# DDR4_SODIMM2.net
KiCad netlist of a schematic drawn in Altium Designer
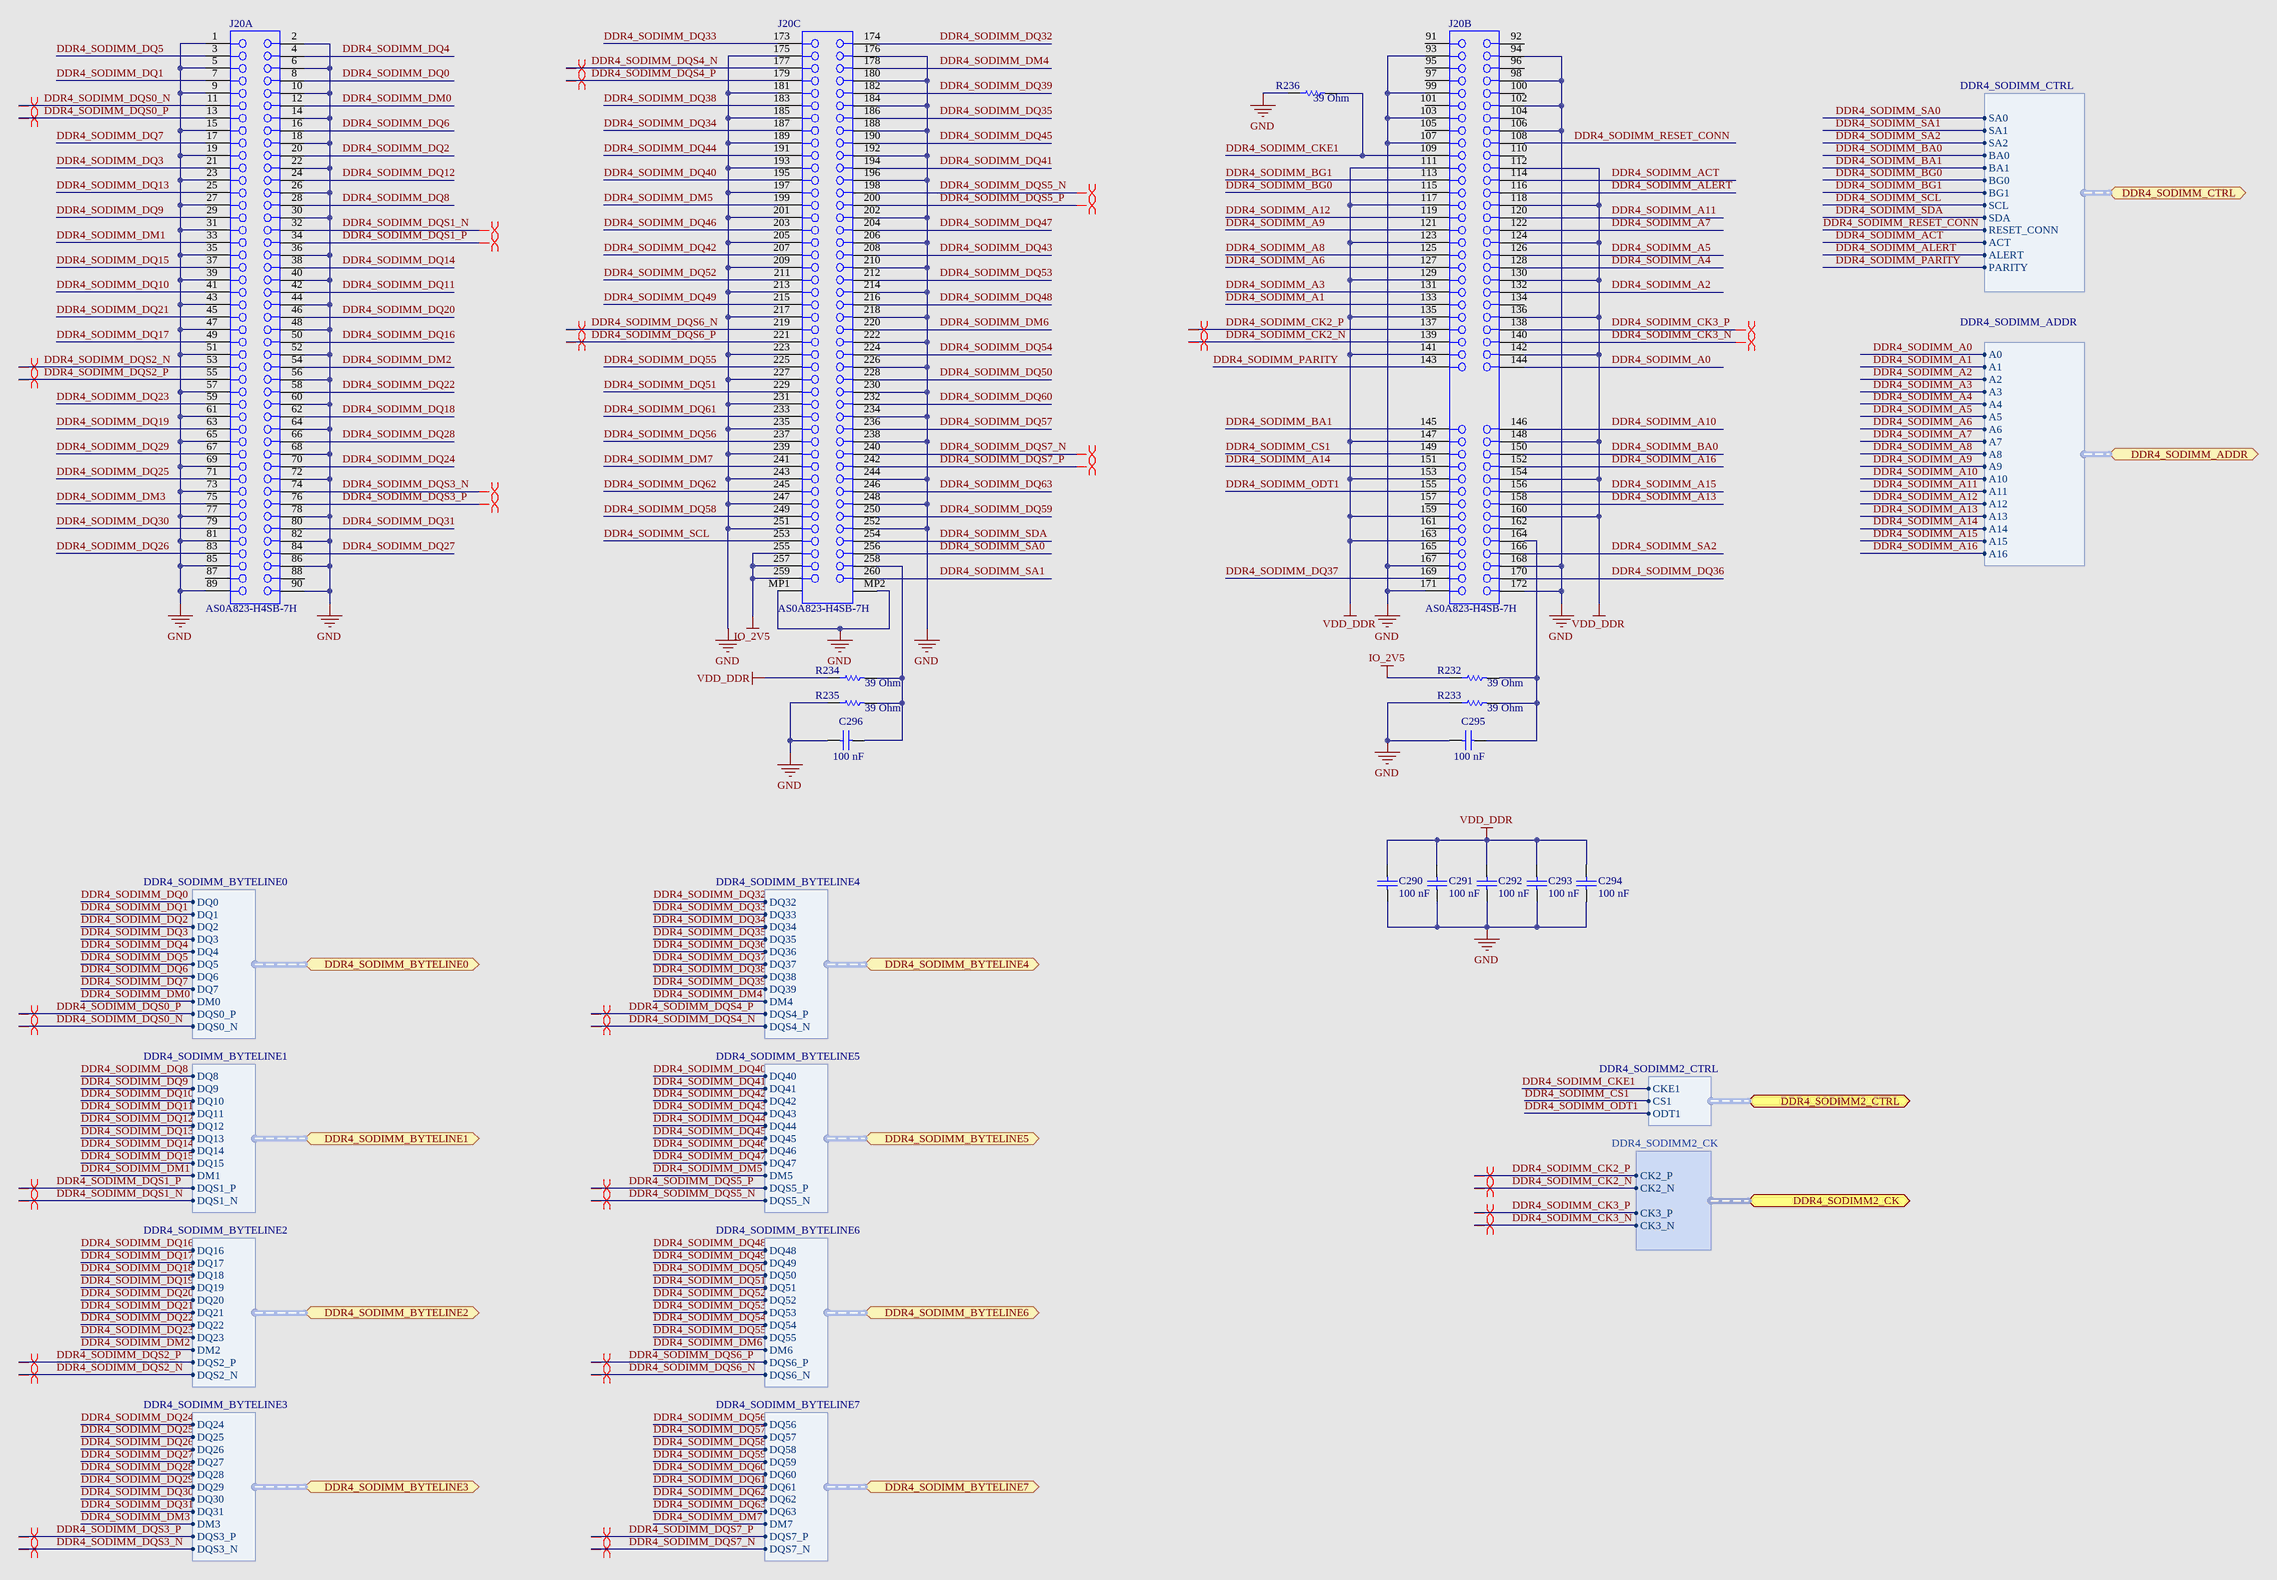
[diagram p0: DDR4_SODIMM2.SchDoc]

(export (version "E")
  (design (tool "Eeschema 10.0.6"))
  (components
    (comp (ref "C290")
      (value "C1005X7R1E104M")
      (footprint "CAPC1005X55X10LL05")
      (description "Chip Capacitor, 0.1 uF, +/- 20%, 25 V, -55 to 125 degC, 0402 (1005 Metric), RoHS, Tape and Reel")
      (fields (field (name "TOLERANCE") "20%") (field (name "CAPACITANCE") "100 nF"))
      (libsource (lib "Altium Content Vault") (part "CAP-NP-2"))
    )
    (comp (ref "C291")
      (value "C1005X7R1E104M")
      (footprint "CAPC1005X55X10LL05")
      (description "Chip Capacitor, 0.1 uF, +/- 20%, 25 V, -55 to 125 degC, 0402 (1005 Metric), RoHS, Tape and Reel")
      (fields (field (name "TOLERANCE") "20%") (field (name "CAPACITANCE") "100 nF"))
      (libsource (lib "Altium Content Vault") (part "CAP-NP-2"))
    )
    (comp (ref "C292")
      (value "C1005X7R1E104M")
      (footprint "CAPC1005X55X10LL05")
      (description "Chip Capacitor, 0.1 uF, +/- 20%, 25 V, -55 to 125 degC, 0402 (1005 Metric), RoHS, Tape and Reel")
      (fields (field (name "TOLERANCE") "20%") (field (name "CAPACITANCE") "100 nF"))
      (libsource (lib "Altium Content Vault") (part "CAP-NP-2"))
    )
    (comp (ref "C293")
      (value "C1005X7R1E104M")
      (footprint "CAPC1005X55X10LL05")
      (description "Chip Capacitor, 0.1 uF, +/- 20%, 25 V, -55 to 125 degC, 0402 (1005 Metric), RoHS, Tape and Reel")
      (fields (field (name "TOLERANCE") "20%") (field (name "CAPACITANCE") "100 nF"))
      (libsource (lib "Altium Content Vault") (part "CAP-NP-2"))
    )
    (comp (ref "C294")
      (value "C1005X7R1E104M")
      (footprint "CAPC1005X55X10LL05")
      (description "Chip Capacitor, 0.1 uF, +/- 20%, 25 V, -55 to 125 degC, 0402 (1005 Metric), RoHS, Tape and Reel")
      (fields (field (name "TOLERANCE") "20%") (field (name "CAPACITANCE") "100 nF"))
      (libsource (lib "Altium Content Vault") (part "CAP-NP-2"))
    )
    (comp (ref "C295")
      (value "C1005X7R1E104M")
      (footprint "CAPC1005X55X10LL05")
      (description "Chip Capacitor, 0.1 uF, +/- 20%, 25 V, -55 to 125 degC, 0402 (1005 Metric), RoHS, Tape and Reel")
      (fields (field (name "TOLERANCE") "20%") (field (name "CAPACITANCE") "100 nF"))
      (libsource (lib "Altium Content Vault") (part "CAP-NP-2"))
    )
    (comp (ref "C296")
      (value "C1005X7R1E104M")
      (footprint "CAPC1005X55X10LL05")
      (description "Chip Capacitor, 0.1 uF, +/- 20%, 25 V, -55 to 125 degC, 0402 (1005 Metric), RoHS, Tape and Reel")
      (fields (field (name "TOLERANCE") "20%") (field (name "CAPACITANCE") "100 nF"))
      (libsource (lib "Altium Content Vault") (part "CAP-NP-2"))
    )
    (comp (ref "J20")
      (value "AS0A823-H4SB-7H")
      (footprint "FOXC-AS0A823-H4SB-7H_V")
      (libsource (lib "") (part "CN-2S-2F-R260_1"))
    )
    (comp (ref "R232")
      (value "NRC04F49R9TRF")
      (footprint "RESC1005X35X25NL8T10")
      (description "Chip Resistor, 39 Ohm, +/- 5%, 0.063 W, -55 to 155 degC, 0402 (1005 Metric), RoHS, Tape and Reel")
      (fields
        (field (name "PARTNUMBER") "RC0402JR-0739RL")
        (field (name "TOLERANCE") "5%")
        (field (name "RESISTANCE") "39 Ohm")
      )
      (libsource (lib "Altium Content Vault") (part "CMP-2002-07994-2"))
    )
    (comp (ref "R233")
      (value "NRC04F49R9TRF")
      (footprint "RESC1005X35X25NL8T10")
      (description "Chip Resistor, 39 Ohm, +/- 5%, 0.063 W, -55 to 155 degC, 0402 (1005 Metric), RoHS, Tape and Reel")
      (fields
        (field (name "PARTNUMBER") "RC0402JR-0739RL")
        (field (name "TOLERANCE") "5%")
        (field (name "RESISTANCE") "39 Ohm")
      )
      (libsource (lib "Altium Content Vault") (part "CMP-2002-07994-2"))
    )
    (comp (ref "R234")
      (value "NRC04F49R9TRF")
      (footprint "RESC1005X35X25NL8T10")
      (description "Chip Resistor, 39 Ohm, +/- 5%, 0.063 W, -55 to 155 degC, 0402 (1005 Metric), RoHS, Tape and Reel")
      (fields
        (field (name "PARTNUMBER") "RC0402JR-0739RL")
        (field (name "TOLERANCE") "5%")
        (field (name "RESISTANCE") "39 Ohm")
      )
      (libsource (lib "Altium Content Vault") (part "CMP-2002-07994-2"))
    )
    (comp (ref "R235")
      (value "NRC04F49R9TRF")
      (footprint "RESC1005X35X25NL8T10")
      (description "Chip Resistor, 39 Ohm, +/- 5%, 0.063 W, -55 to 155 degC, 0402 (1005 Metric), RoHS, Tape and Reel")
      (fields
        (field (name "PARTNUMBER") "RC0402JR-0739RL")
        (field (name "TOLERANCE") "5%")
        (field (name "RESISTANCE") "39 Ohm")
      )
      (libsource (lib "Altium Content Vault") (part "CMP-2002-07994-2"))
    )
    (comp (ref "R236")
      (value "RC0402JR-0739RL")
      (footprint "RESC1005X40X25NL5T10")
      (description "Chip Resistor, 39 Ohm, +/- 5%, 0.063 W, -55 to 155 degC, 0402 (1005 Metric), RoHS, Tape and Reel")
      (fields (field (name "TOLERANCE") "5%") (field (name "RESISTANCE") "39 Ohm"))
      (libsource (lib "Altium Content Vault") (part "CMP-2002-07994-2"))
    )
  )
  (nets
    (net (code "13") (name "/DDR4_SODIMM_A0") (class "Default")
      (node (ref "J20") (pin "144") (pinfunction "144_144") (pintype "passive"))
    )
    (net (code "14") (name "/DDR4_SODIMM_A1") (class "Default")
      (node (ref "J20") (pin "133") (pinfunction "133_133") (pintype "passive"))
    )
    (net (code "15") (name "/DDR4_SODIMM_A2") (class "Default")
      (node (ref "J20") (pin "132") (pinfunction "132_132") (pintype "passive"))
    )
    (net (code "16") (name "/DDR4_SODIMM_A3") (class "Default")
      (node (ref "J20") (pin "131") (pinfunction "131_131") (pintype "passive"))
    )
    (net (code "17") (name "/DDR4_SODIMM_A4") (class "Default")
      (node (ref "J20") (pin "128") (pinfunction "128_128") (pintype "passive"))
    )
    (net (code "18") (name "/DDR4_SODIMM_A5") (class "Default")
      (node (ref "J20") (pin "126") (pinfunction "126_126") (pintype "passive"))
    )
    (net (code "19") (name "/DDR4_SODIMM_A6") (class "Default")
      (node (ref "J20") (pin "127") (pinfunction "127_127") (pintype "passive"))
    )
    (net (code "20") (name "/DDR4_SODIMM_A7") (class "Default")
      (node (ref "J20") (pin "122") (pinfunction "122_122") (pintype "passive"))
    )
    (net (code "21") (name "/DDR4_SODIMM_A8") (class "Default")
      (node (ref "J20") (pin "125") (pinfunction "125_125") (pintype "passive"))
    )
    (net (code "22") (name "/DDR4_SODIMM_A9") (class "Default")
      (node (ref "J20") (pin "121") (pinfunction "121_121") (pintype "passive"))
    )
    (net (code "23") (name "/DDR4_SODIMM_A10") (class "Default")
      (node (ref "J20") (pin "146") (pinfunction "146_146") (pintype "passive"))
    )
    (net (code "24") (name "/DDR4_SODIMM_A11") (class "Default")
      (node (ref "J20") (pin "120") (pinfunction "120_120") (pintype "passive"))
    )
    (net (code "25") (name "/DDR4_SODIMM_A12") (class "Default")
      (node (ref "J20") (pin "119") (pinfunction "119_119") (pintype "passive"))
    )
    (net (code "26") (name "/DDR4_SODIMM_A13") (class "Default")
      (node (ref "J20") (pin "158") (pinfunction "158_158") (pintype "passive"))
    )
    (net (code "27") (name "/DDR4_SODIMM_A14") (class "Default")
      (node (ref "J20") (pin "151") (pinfunction "151_151") (pintype "passive"))
    )
    (net (code "28") (name "/DDR4_SODIMM_A15") (class "Default")
      (node (ref "J20") (pin "156") (pinfunction "156_156") (pintype "passive"))
    )
    (net (code "29") (name "/DDR4_SODIMM_A16") (class "Default")
      (node (ref "J20") (pin "152") (pinfunction "152_152") (pintype "passive"))
    )
    (net (code "30") (name "/DDR4_SODIMM_ACT") (class "Default")
      (node (ref "J20") (pin "114") (pinfunction "114_114") (pintype "passive"))
    )
    (net (code "31") (name "/DDR4_SODIMM_ALERT") (class "Default")
      (node (ref "J20") (pin "116") (pinfunction "116_116") (pintype "passive"))
    )
    (net (code "32") (name "/DDR4_SODIMM_BA0") (class "Default")
      (node (ref "J20") (pin "150") (pinfunction "150_150") (pintype "passive"))
    )
    (net (code "33") (name "/DDR4_SODIMM_BA1") (class "Default")
      (node (ref "J20") (pin "145") (pinfunction "145_145") (pintype "passive"))
    )
    (net (code "34") (name "/DDR4_SODIMM_BG0") (class "Default")
      (node (ref "J20") (pin "115") (pinfunction "115_115") (pintype "passive"))
    )
    (net (code "35") (name "/DDR4_SODIMM_BG1") (class "Default")
      (node (ref "J20") (pin "113") (pinfunction "113_113") (pintype "passive"))
    )
    (net (code "36") (name "/DDR4_SODIMM_CK2_N") (class "Default")
      (node (ref "J20") (pin "139") (pinfunction "139_139") (pintype "passive"))
    )
    (net (code "37") (name "/DDR4_SODIMM_CK2_P") (class "Default")
      (node (ref "J20") (pin "137") (pinfunction "137_137") (pintype "passive"))
    )
    (net (code "38") (name "/DDR4_SODIMM_CK3_N") (class "Default")
      (node (ref "J20") (pin "140") (pinfunction "140_140") (pintype "passive"))
    )
    (net (code "39") (name "/DDR4_SODIMM_CK3_P") (class "Default")
      (node (ref "J20") (pin "138") (pinfunction "138_138") (pintype "passive"))
    )
    (net (code "40") (name "/DDR4_SODIMM_CKE1") (class "Default")
      (node (ref "J20") (pin "109") (pinfunction "109_109") (pintype "passive"))
      (node (ref "R236") (pin "2") (pinfunction "2_2") (pintype "passive"))
    )
    (net (code "41") (name "/DDR4_SODIMM_CS1") (class "Default")
      (node (ref "J20") (pin "149") (pinfunction "149_149") (pintype "passive"))
    )
    (net (code "42") (name "/DDR4_SODIMM_DM0") (class "Default")
      (node (ref "J20") (pin "12") (pinfunction "12_12") (pintype "passive"))
    )
    (net (code "43") (name "/DDR4_SODIMM_DM1") (class "Default")
      (node (ref "J20") (pin "33") (pinfunction "33_33") (pintype "passive"))
    )
    (net (code "44") (name "/DDR4_SODIMM_DM2") (class "Default")
      (node (ref "J20") (pin "54") (pinfunction "54_54") (pintype "passive"))
    )
    (net (code "45") (name "/DDR4_SODIMM_DM3") (class "Default")
      (node (ref "J20") (pin "75") (pinfunction "75_75") (pintype "passive"))
    )
    (net (code "46") (name "/DDR4_SODIMM_DM4") (class "Default")
      (node (ref "J20") (pin "178") (pinfunction "178_178") (pintype "passive"))
    )
    (net (code "47") (name "/DDR4_SODIMM_DM5") (class "Default")
      (node (ref "J20") (pin "199") (pinfunction "199_199") (pintype "passive"))
    )
    (net (code "48") (name "/DDR4_SODIMM_DM6") (class "Default")
      (node (ref "J20") (pin "220") (pinfunction "220_220") (pintype "passive"))
    )
    (net (code "49") (name "/DDR4_SODIMM_DM7") (class "Default")
      (node (ref "J20") (pin "241") (pinfunction "241_241") (pintype "passive"))
    )
    (net (code "50") (name "/DDR4_SODIMM_DQ0") (class "Default")
      (node (ref "J20") (pin "8") (pinfunction "8_8") (pintype "passive"))
    )
    (net (code "51") (name "/DDR4_SODIMM_DQ1") (class "Default")
      (node (ref "J20") (pin "7") (pinfunction "7_7") (pintype "passive"))
    )
    (net (code "52") (name "/DDR4_SODIMM_DQ2") (class "Default")
      (node (ref "J20") (pin "20") (pinfunction "20_20") (pintype "passive"))
    )
    (net (code "53") (name "/DDR4_SODIMM_DQ3") (class "Default")
      (node (ref "J20") (pin "21") (pinfunction "21_21") (pintype "passive"))
    )
    (net (code "54") (name "/DDR4_SODIMM_DQ4") (class "Default")
      (node (ref "J20") (pin "4") (pinfunction "4_4") (pintype "passive"))
    )
    (net (code "55") (name "/DDR4_SODIMM_DQ5") (class "Default")
      (node (ref "J20") (pin "3") (pinfunction "3_3") (pintype "passive"))
    )
    (net (code "56") (name "/DDR4_SODIMM_DQ6") (class "Default")
      (node (ref "J20") (pin "16") (pinfunction "16_16") (pintype "passive"))
    )
    (net (code "57") (name "/DDR4_SODIMM_DQ7") (class "Default")
      (node (ref "J20") (pin "17") (pinfunction "17_17") (pintype "passive"))
    )
    (net (code "58") (name "/DDR4_SODIMM_DQ8") (class "Default")
      (node (ref "J20") (pin "28") (pinfunction "28_28") (pintype "passive"))
    )
    (net (code "59") (name "/DDR4_SODIMM_DQ9") (class "Default")
      (node (ref "J20") (pin "29") (pinfunction "29_29") (pintype "passive"))
    )
    (net (code "60") (name "/DDR4_SODIMM_DQ10") (class "Default")
      (node (ref "J20") (pin "41") (pinfunction "41_41") (pintype "passive"))
    )
    (net (code "61") (name "/DDR4_SODIMM_DQ11") (class "Default")
      (node (ref "J20") (pin "42") (pinfunction "42_42") (pintype "passive"))
    )
    (net (code "62") (name "/DDR4_SODIMM_DQ12") (class "Default")
      (node (ref "J20") (pin "24") (pinfunction "24_24") (pintype "passive"))
    )
    (net (code "63") (name "/DDR4_SODIMM_DQ13") (class "Default")
      (node (ref "J20") (pin "25") (pinfunction "25_25") (pintype "passive"))
    )
    (net (code "64") (name "/DDR4_SODIMM_DQ14") (class "Default")
      (node (ref "J20") (pin "38") (pinfunction "38_38") (pintype "passive"))
    )
    (net (code "65") (name "/DDR4_SODIMM_DQ15") (class "Default")
      (node (ref "J20") (pin "37") (pinfunction "37_37") (pintype "passive"))
    )
    (net (code "66") (name "/DDR4_SODIMM_DQ16") (class "Default")
      (node (ref "J20") (pin "50") (pinfunction "50_50") (pintype "passive"))
    )
    (net (code "67") (name "/DDR4_SODIMM_DQ17") (class "Default")
      (node (ref "J20") (pin "49") (pinfunction "49_49") (pintype "passive"))
    )
    (net (code "68") (name "/DDR4_SODIMM_DQ18") (class "Default")
      (node (ref "J20") (pin "62") (pinfunction "62_62") (pintype "passive"))
    )
    (net (code "69") (name "/DDR4_SODIMM_DQ19") (class "Default")
      (node (ref "J20") (pin "63") (pinfunction "63_63") (pintype "passive"))
    )
    (net (code "70") (name "/DDR4_SODIMM_DQ20") (class "Default")
      (node (ref "J20") (pin "46") (pinfunction "46_46") (pintype "passive"))
    )
    (net (code "71") (name "/DDR4_SODIMM_DQ21") (class "Default")
      (node (ref "J20") (pin "45") (pinfunction "45_45") (pintype "passive"))
    )
    (net (code "72") (name "/DDR4_SODIMM_DQ22") (class "Default")
      (node (ref "J20") (pin "58") (pinfunction "58_58") (pintype "passive"))
    )
    (net (code "73") (name "/DDR4_SODIMM_DQ23") (class "Default")
      (node (ref "J20") (pin "59") (pinfunction "59_59") (pintype "passive"))
    )
    (net (code "74") (name "/DDR4_SODIMM_DQ24") (class "Default")
      (node (ref "J20") (pin "70") (pinfunction "70_70") (pintype "passive"))
    )
    (net (code "75") (name "/DDR4_SODIMM_DQ25") (class "Default")
      (node (ref "J20") (pin "71") (pinfunction "71_71") (pintype "passive"))
    )
    (net (code "76") (name "/DDR4_SODIMM_DQ26") (class "Default")
      (node (ref "J20") (pin "83") (pinfunction "83_83") (pintype "passive"))
    )
    (net (code "77") (name "/DDR4_SODIMM_DQ27") (class "Default")
      (node (ref "J20") (pin "84") (pinfunction "84_84") (pintype "passive"))
    )
    (net (code "78") (name "/DDR4_SODIMM_DQ28") (class "Default")
      (node (ref "J20") (pin "66") (pinfunction "66_66") (pintype "passive"))
    )
    (net (code "79") (name "/DDR4_SODIMM_DQ29") (class "Default")
      (node (ref "J20") (pin "67") (pinfunction "67_67") (pintype "passive"))
    )
    (net (code "80") (name "/DDR4_SODIMM_DQ30") (class "Default")
      (node (ref "J20") (pin "79") (pinfunction "79_79") (pintype "passive"))
    )
    (net (code "81") (name "/DDR4_SODIMM_DQ31") (class "Default")
      (node (ref "J20") (pin "80") (pinfunction "80_80") (pintype "passive"))
    )
    (net (code "82") (name "/DDR4_SODIMM_DQ32") (class "Default")
      (node (ref "J20") (pin "174") (pinfunction "174_174") (pintype "passive"))
    )
    (net (code "83") (name "/DDR4_SODIMM_DQ33") (class "Default")
      (node (ref "J20") (pin "173") (pinfunction "173_173") (pintype "passive"))
    )
    (net (code "84") (name "/DDR4_SODIMM_DQ34") (class "Default")
      (node (ref "J20") (pin "187") (pinfunction "187_187") (pintype "passive"))
    )
    (net (code "85") (name "/DDR4_SODIMM_DQ35") (class "Default")
      (node (ref "J20") (pin "186") (pinfunction "186_186") (pintype "passive"))
    )
    (net (code "86") (name "/DDR4_SODIMM_DQ36") (class "Default")
      (node (ref "J20") (pin "170") (pinfunction "170_170") (pintype "passive"))
    )
    (net (code "87") (name "/DDR4_SODIMM_DQ37") (class "Default")
      (node (ref "J20") (pin "169") (pinfunction "169_169") (pintype "passive"))
    )
    (net (code "88") (name "/DDR4_SODIMM_DQ38") (class "Default")
      (node (ref "J20") (pin "183") (pinfunction "183_183") (pintype "passive"))
    )
    (net (code "89") (name "/DDR4_SODIMM_DQ39") (class "Default")
      (node (ref "J20") (pin "182") (pinfunction "182_182") (pintype "passive"))
    )
    (net (code "90") (name "/DDR4_SODIMM_DQ40") (class "Default")
      (node (ref "J20") (pin "195") (pinfunction "195_195") (pintype "passive"))
    )
    (net (code "91") (name "/DDR4_SODIMM_DQ41") (class "Default")
      (node (ref "J20") (pin "194") (pinfunction "194_194") (pintype "passive"))
    )
    (net (code "92") (name "/DDR4_SODIMM_DQ42") (class "Default")
      (node (ref "J20") (pin "207") (pinfunction "207_207") (pintype "passive"))
    )
    (net (code "93") (name "/DDR4_SODIMM_DQ43") (class "Default")
      (node (ref "J20") (pin "208") (pinfunction "208_208") (pintype "passive"))
    )
    (net (code "94") (name "/DDR4_SODIMM_DQ44") (class "Default")
      (node (ref "J20") (pin "191") (pinfunction "191_191") (pintype "passive"))
    )
    (net (code "95") (name "/DDR4_SODIMM_DQ45") (class "Default")
      (node (ref "J20") (pin "190") (pinfunction "190_190") (pintype "passive"))
    )
    (net (code "96") (name "/DDR4_SODIMM_DQ46") (class "Default")
      (node (ref "J20") (pin "203") (pinfunction "203_203") (pintype "passive"))
    )
    (net (code "97") (name "/DDR4_SODIMM_DQ47") (class "Default")
      (node (ref "J20") (pin "204") (pinfunction "204_204") (pintype "passive"))
    )
    (net (code "98") (name "/DDR4_SODIMM_DQ48") (class "Default")
      (node (ref "J20") (pin "216") (pinfunction "216_216") (pintype "passive"))
    )
    (net (code "99") (name "/DDR4_SODIMM_DQ49") (class "Default")
      (node (ref "J20") (pin "215") (pinfunction "215_215") (pintype "passive"))
    )
    (net (code "100") (name "/DDR4_SODIMM_DQ50") (class "Default")
      (node (ref "J20") (pin "228") (pinfunction "228_228") (pintype "passive"))
    )
    (net (code "101") (name "/DDR4_SODIMM_DQ51") (class "Default")
      (node (ref "J20") (pin "229") (pinfunction "229_229") (pintype "passive"))
    )
    (net (code "102") (name "/DDR4_SODIMM_DQ52") (class "Default")
      (node (ref "J20") (pin "211") (pinfunction "211_211") (pintype "passive"))
    )
    (net (code "103") (name "/DDR4_SODIMM_DQ53") (class "Default")
      (node (ref "J20") (pin "212") (pinfunction "212_212") (pintype "passive"))
    )
    (net (code "104") (name "/DDR4_SODIMM_DQ54") (class "Default")
      (node (ref "J20") (pin "224") (pinfunction "224_224") (pintype "passive"))
    )
    (net (code "105") (name "/DDR4_SODIMM_DQ55") (class "Default")
      (node (ref "J20") (pin "225") (pinfunction "225_225") (pintype "passive"))
    )
    (net (code "106") (name "/DDR4_SODIMM_DQ56") (class "Default")
      (node (ref "J20") (pin "237") (pinfunction "237_237") (pintype "passive"))
    )
    (net (code "107") (name "/DDR4_SODIMM_DQ57") (class "Default")
      (node (ref "J20") (pin "236") (pinfunction "236_236") (pintype "passive"))
    )
    (net (code "108") (name "/DDR4_SODIMM_DQ58") (class "Default")
      (node (ref "J20") (pin "249") (pinfunction "249_249") (pintype "passive"))
    )
    (net (code "109") (name "/DDR4_SODIMM_DQ59") (class "Default")
      (node (ref "J20") (pin "250") (pinfunction "250_250") (pintype "passive"))
    )
    (net (code "110") (name "/DDR4_SODIMM_DQ60") (class "Default")
      (node (ref "J20") (pin "232") (pinfunction "232_232") (pintype "passive"))
    )
    (net (code "111") (name "/DDR4_SODIMM_DQ61") (class "Default")
      (node (ref "J20") (pin "233") (pinfunction "233_233") (pintype "passive"))
    )
    (net (code "112") (name "/DDR4_SODIMM_DQ62") (class "Default")
      (node (ref "J20") (pin "245") (pinfunction "245_245") (pintype "passive"))
    )
    (net (code "113") (name "/DDR4_SODIMM_DQ63") (class "Default")
      (node (ref "J20") (pin "246") (pinfunction "246_246") (pintype "passive"))
    )
    (net (code "114") (name "/DDR4_SODIMM_DQS0_N") (class "Default")
      (node (ref "J20") (pin "11") (pinfunction "11_11") (pintype "passive"))
    )
    (net (code "115") (name "/DDR4_SODIMM_DQS0_P") (class "Default")
      (node (ref "J20") (pin "13") (pinfunction "13_13") (pintype "passive"))
    )
    (net (code "116") (name "/DDR4_SODIMM_DQS1_N") (class "Default")
      (node (ref "J20") (pin "32") (pinfunction "32_32") (pintype "passive"))
    )
    (net (code "117") (name "/DDR4_SODIMM_DQS1_P") (class "Default")
      (node (ref "J20") (pin "34") (pinfunction "34_34") (pintype "passive"))
    )
    (net (code "118") (name "/DDR4_SODIMM_DQS2_N") (class "Default")
      (node (ref "J20") (pin "53") (pinfunction "53_53") (pintype "passive"))
    )
    (net (code "119") (name "/DDR4_SODIMM_DQS2_P") (class "Default")
      (node (ref "J20") (pin "55") (pinfunction "55_55") (pintype "passive"))
    )
    (net (code "120") (name "/DDR4_SODIMM_DQS3_N") (class "Default")
      (node (ref "J20") (pin "74") (pinfunction "74_74") (pintype "passive"))
    )
    (net (code "121") (name "/DDR4_SODIMM_DQS3_P") (class "Default")
      (node (ref "J20") (pin "76") (pinfunction "76_76") (pintype "passive"))
    )
    (net (code "122") (name "/DDR4_SODIMM_DQS4_N") (class "Default")
      (node (ref "J20") (pin "177") (pinfunction "177_177") (pintype "passive"))
    )
    (net (code "123") (name "/DDR4_SODIMM_DQS4_P") (class "Default")
      (node (ref "J20") (pin "179") (pinfunction "179_179") (pintype "passive"))
    )
    (net (code "124") (name "/DDR4_SODIMM_DQS5_N") (class "Default")
      (node (ref "J20") (pin "198") (pinfunction "198_198") (pintype "passive"))
    )
    (net (code "125") (name "/DDR4_SODIMM_DQS5_P") (class "Default")
      (node (ref "J20") (pin "200") (pinfunction "200_200") (pintype "passive"))
    )
    (net (code "126") (name "/DDR4_SODIMM_DQS6_N") (class "Default")
      (node (ref "J20") (pin "219") (pinfunction "219_219") (pintype "passive"))
    )
    (net (code "127") (name "/DDR4_SODIMM_DQS6_P") (class "Default")
      (node (ref "J20") (pin "221") (pinfunction "221_221") (pintype "passive"))
    )
    (net (code "128") (name "/DDR4_SODIMM_DQS7_N") (class "Default")
      (node (ref "J20") (pin "240") (pinfunction "240_240") (pintype "passive"))
    )
    (net (code "129") (name "/DDR4_SODIMM_DQS7_P") (class "Default")
      (node (ref "J20") (pin "242") (pinfunction "242_242") (pintype "passive"))
    )
    (net (code "130") (name "/DDR4_SODIMM_ODT1") (class "Default")
      (node (ref "J20") (pin "155") (pinfunction "155_155") (pintype "passive"))
    )
    (net (code "131") (name "/DDR4_SODIMM_PARITY") (class "Default")
      (node (ref "J20") (pin "143") (pinfunction "143_143") (pintype "passive"))
    )
    (net (code "132") (name "/DDR4_SODIMM_RESET_CONN") (class "Default")
      (node (ref "J20") (pin "108") (pinfunction "108_108") (pintype "passive"))
    )
    (net (code "133") (name "/DDR4_SODIMM_SA0") (class "Default")
      (node (ref "J20") (pin "256") (pinfunction "256_256") (pintype "passive"))
    )
    (net (code "134") (name "/DDR4_SODIMM_SA1") (class "Default")
      (node (ref "J20") (pin "260") (pinfunction "260_260") (pintype "passive"))
    )
    (net (code "135") (name "/DDR4_SODIMM_SA2") (class "Default")
      (node (ref "J20") (pin "166") (pinfunction "166_166") (pintype "passive"))
    )
    (net (code "136") (name "/DDR4_SODIMM_SCL") (class "Default")
      (node (ref "J20") (pin "253") (pinfunction "253_253") (pintype "passive"))
    )
    (net (code "137") (name "/DDR4_SODIMM_SDA") (class "Default")
      (node (ref "J20") (pin "254") (pinfunction "254_254") (pintype "passive"))
    )
    (net (code "150") (name "GND") (class "Default")
      (node (ref "C290") (pin "2") (pinfunction "2_2") (pintype "passive"))
      (node (ref "C291") (pin "2") (pinfunction "2_2") (pintype "passive"))
      (node (ref "C292") (pin "2") (pinfunction "2_2") (pintype "passive"))
      (node (ref "C293") (pin "2") (pinfunction "2_2") (pintype "passive"))
      (node (ref "C294") (pin "2") (pinfunction "2_2") (pintype "passive"))
      (node (ref "C295") (pin "2") (pinfunction "2_2") (pintype "passive"))
      (node (ref "C296") (pin "2") (pinfunction "2_2") (pintype "passive"))
      (node (ref "J20") (pin "1") (pinfunction "1_1") (pintype "passive"))
      (node (ref "J20") (pin "10") (pinfunction "10_10") (pintype "passive"))
      (node (ref "J20") (pin "102") (pinfunction "102_102") (pintype "passive"))
      (node (ref "J20") (pin "103") (pinfunction "103_103") (pintype "passive"))
      (node (ref "J20") (pin "106") (pinfunction "106_106") (pintype "passive"))
      (node (ref "J20") (pin "107") (pinfunction "107_107") (pintype "passive"))
      (node (ref "J20") (pin "14") (pinfunction "14_14") (pintype "passive"))
      (node (ref "J20") (pin "15") (pinfunction "15_15") (pintype "passive"))
      (node (ref "J20") (pin "167") (pinfunction "167_167") (pintype "passive"))
      (node (ref "J20") (pin "168") (pinfunction "168_168") (pintype "passive"))
      (node (ref "J20") (pin "171") (pinfunction "171_171") (pintype "passive"))
      (node (ref "J20") (pin "172") (pinfunction "172_172") (pintype "passive"))
      (node (ref "J20") (pin "175") (pinfunction "175_175") (pintype "passive"))
      (node (ref "J20") (pin "176") (pinfunction "176_176") (pintype "passive"))
      (node (ref "J20") (pin "18") (pinfunction "18_18") (pintype "passive"))
      (node (ref "J20") (pin "180") (pinfunction "180_180") (pintype "passive"))
      (node (ref "J20") (pin "181") (pinfunction "181_181") (pintype "passive"))
      (node (ref "J20") (pin "184") (pinfunction "184_184") (pintype "passive"))
      (node (ref "J20") (pin "185") (pinfunction "185_185") (pintype "passive"))
      (node (ref "J20") (pin "188") (pinfunction "188_188") (pintype "passive"))
      (node (ref "J20") (pin "189") (pinfunction "189_189") (pintype "passive"))
      (node (ref "J20") (pin "19") (pinfunction "19_19") (pintype "passive"))
      (node (ref "J20") (pin "192") (pinfunction "192_192") (pintype "passive"))
      (node (ref "J20") (pin "193") (pinfunction "193_193") (pintype "passive"))
      (node (ref "J20") (pin "196") (pinfunction "196_196") (pintype "passive"))
      (node (ref "J20") (pin "197") (pinfunction "197_197") (pintype "passive"))
      (node (ref "J20") (pin "2") (pinfunction "2_2") (pintype "passive"))
      (node (ref "J20") (pin "201") (pinfunction "201_201") (pintype "passive"))
      (node (ref "J20") (pin "202") (pinfunction "202_202") (pintype "passive"))
      (node (ref "J20") (pin "205") (pinfunction "205_205") (pintype "passive"))
      (node (ref "J20") (pin "206") (pinfunction "206_206") (pintype "passive"))
      (node (ref "J20") (pin "209") (pinfunction "209_209") (pintype "passive"))
      (node (ref "J20") (pin "210") (pinfunction "210_210") (pintype "passive"))
      (node (ref "J20") (pin "213") (pinfunction "213_213") (pintype "passive"))
      (node (ref "J20") (pin "214") (pinfunction "214_214") (pintype "passive"))
      (node (ref "J20") (pin "217") (pinfunction "217_217") (pintype "passive"))
      (node (ref "J20") (pin "218") (pinfunction "218_218") (pintype "passive"))
      (node (ref "J20") (pin "22") (pinfunction "22_22") (pintype "passive"))
      (node (ref "J20") (pin "222") (pinfunction "222_222") (pintype "passive"))
      (node (ref "J20") (pin "223") (pinfunction "223_223") (pintype "passive"))
      (node (ref "J20") (pin "226") (pinfunction "226_226") (pintype "passive"))
      (node (ref "J20") (pin "227") (pinfunction "227_227") (pintype "passive"))
      (node (ref "J20") (pin "23") (pinfunction "23_23") (pintype "passive"))
      (node (ref "J20") (pin "230") (pinfunction "230_230") (pintype "passive"))
      (node (ref "J20") (pin "231") (pinfunction "231_231") (pintype "passive"))
      (node (ref "J20") (pin "234") (pinfunction "234_234") (pintype "passive"))
      (node (ref "J20") (pin "235") (pinfunction "235_235") (pintype "passive"))
      (node (ref "J20") (pin "238") (pinfunction "238_238") (pintype "passive"))
      (node (ref "J20") (pin "239") (pinfunction "239_239") (pintype "passive"))
      (node (ref "J20") (pin "243") (pinfunction "243_243") (pintype "passive"))
      (node (ref "J20") (pin "244") (pinfunction "244_244") (pintype "passive"))
      (node (ref "J20") (pin "247") (pinfunction "247_247") (pintype "passive"))
      (node (ref "J20") (pin "248") (pinfunction "248_248") (pintype "passive"))
      (node (ref "J20") (pin "251") (pinfunction "251_251") (pintype "passive"))
      (node (ref "J20") (pin "252") (pinfunction "252_252") (pintype "passive"))
      (node (ref "J20") (pin "26") (pinfunction "26_26") (pintype "passive"))
      (node (ref "J20") (pin "27") (pinfunction "27_27") (pintype "passive"))
      (node (ref "J20") (pin "30") (pinfunction "30_30") (pintype "passive"))
      (node (ref "J20") (pin "31") (pinfunction "31_31") (pintype "passive"))
      (node (ref "J20") (pin "35") (pinfunction "35_35") (pintype "passive"))
      (node (ref "J20") (pin "36") (pinfunction "36_36") (pintype "passive"))
      (node (ref "J20") (pin "39") (pinfunction "39_39") (pintype "passive"))
      (node (ref "J20") (pin "40") (pinfunction "40_40") (pintype "passive"))
      (node (ref "J20") (pin "43") (pinfunction "43_43") (pintype "passive"))
      (node (ref "J20") (pin "44") (pinfunction "44_44") (pintype "passive"))
      (node (ref "J20") (pin "47") (pinfunction "47_47") (pintype "passive"))
      (node (ref "J20") (pin "48") (pinfunction "48_48") (pintype "passive"))
      (node (ref "J20") (pin "5") (pinfunction "5_5") (pintype "passive"))
      (node (ref "J20") (pin "51") (pinfunction "51_51") (pintype "passive"))
      (node (ref "J20") (pin "52") (pinfunction "52_52") (pintype "passive"))
      (node (ref "J20") (pin "56") (pinfunction "56_56") (pintype "passive"))
      (node (ref "J20") (pin "57") (pinfunction "57_57") (pintype "passive"))
      (node (ref "J20") (pin "6") (pinfunction "6_6") (pintype "passive"))
      (node (ref "J20") (pin "60") (pinfunction "60_60") (pintype "passive"))
      (node (ref "J20") (pin "61") (pinfunction "61_61") (pintype "passive"))
      (node (ref "J20") (pin "64") (pinfunction "64_64") (pintype "passive"))
      (node (ref "J20") (pin "65") (pinfunction "65_65") (pintype "passive"))
      (node (ref "J20") (pin "68") (pinfunction "68_68") (pintype "passive"))
      (node (ref "J20") (pin "69") (pinfunction "69_69") (pintype "passive"))
      (node (ref "J20") (pin "72") (pinfunction "72_72") (pintype "passive"))
      (node (ref "J20") (pin "73") (pinfunction "73_73") (pintype "passive"))
      (node (ref "J20") (pin "77") (pinfunction "77_77") (pintype "passive"))
      (node (ref "J20") (pin "78") (pinfunction "78_78") (pintype "passive"))
      (node (ref "J20") (pin "81") (pinfunction "81_81") (pintype "passive"))
      (node (ref "J20") (pin "82") (pinfunction "82_82") (pintype "passive"))
      (node (ref "J20") (pin "85") (pinfunction "85_85") (pintype "passive"))
      (node (ref "J20") (pin "86") (pinfunction "86_86") (pintype "passive"))
      (node (ref "J20") (pin "89") (pinfunction "89_89") (pintype "passive"))
      (node (ref "J20") (pin "9") (pinfunction "9_9") (pintype "passive"))
      (node (ref "J20") (pin "90") (pinfunction "90_90") (pintype "passive"))
      (node (ref "J20") (pin "93") (pinfunction "93_93") (pintype "passive"))
      (node (ref "J20") (pin "94") (pinfunction "94_94") (pintype "passive"))
      (node (ref "J20") (pin "98") (pinfunction "98_98") (pintype "passive"))
      (node (ref "J20") (pin "99") (pinfunction "99_99") (pintype "passive"))
      (node (ref "J20") (pin "MP1") (pinfunction "MP1_MP1") (pintype "passive"))
      (node (ref "J20") (pin "MP2") (pinfunction "MP2_MP2") (pintype "passive"))
      (node (ref "R233") (pin "1") (pinfunction "1_1") (pintype "passive"))
      (node (ref "R235") (pin "1") (pinfunction "1_1") (pintype "passive"))
      (node (ref "R236") (pin "1") (pinfunction "1_1") (pintype "passive"))
    )
    (net (code "151") (name "IO_2V5") (class "Default")
      (node (ref "J20") (pin "255") (pinfunction "255_255") (pintype "passive"))
      (node (ref "J20") (pin "257") (pinfunction "257_257") (pintype "passive"))
      (node (ref "J20") (pin "259") (pinfunction "259_259") (pintype "passive"))
      (node (ref "R232") (pin "1") (pinfunction "1_1") (pintype "passive"))
    )
    (net (code "152") (name "Net-(C295-Pad1)") (class "Default")
      (node (ref "C295") (pin "1") (pinfunction "1_1") (pintype "passive"))
      (node (ref "J20") (pin "164") (pinfunction "164_164") (pintype "passive"))
      (node (ref "R232") (pin "2") (pinfunction "2_2") (pintype "passive"))
      (node (ref "R233") (pin "2") (pinfunction "2_2") (pintype "passive"))
    )
    (net (code "153") (name "Net-(C296-Pad1)") (class "Default")
      (node (ref "C296") (pin "1") (pinfunction "1_1") (pintype "passive"))
      (node (ref "J20") (pin "258") (pinfunction "258_258") (pintype "passive"))
      (node (ref "R234") (pin "2") (pinfunction "2_2") (pintype "passive"))
      (node (ref "R235") (pin "2") (pinfunction "2_2") (pintype "passive"))
    )
    (net (code "154") (name "VDD_DDR") (class "Default")
      (node (ref "C290") (pin "1") (pinfunction "1_1") (pintype "passive"))
      (node (ref "C291") (pin "1") (pinfunction "1_1") (pintype "passive"))
      (node (ref "C292") (pin "1") (pinfunction "1_1") (pintype "passive"))
      (node (ref "C293") (pin "1") (pinfunction "1_1") (pintype "passive"))
      (node (ref "C294") (pin "1") (pinfunction "1_1") (pintype "passive"))
      (node (ref "J20") (pin "111") (pinfunction "111_111") (pintype "passive"))
      (node (ref "J20") (pin "112") (pinfunction "112_112") (pintype "passive"))
      (node (ref "J20") (pin "117") (pinfunction "117_117") (pintype "passive"))
      (node (ref "J20") (pin "118") (pinfunction "118_118") (pintype "passive"))
      (node (ref "J20") (pin "123") (pinfunction "123_123") (pintype "passive"))
      (node (ref "J20") (pin "124") (pinfunction "124_124") (pintype "passive"))
      (node (ref "J20") (pin "129") (pinfunction "129_129") (pintype "passive"))
      (node (ref "J20") (pin "130") (pinfunction "130_130") (pintype "passive"))
      (node (ref "J20") (pin "135") (pinfunction "135_135") (pintype "passive"))
      (node (ref "J20") (pin "136") (pinfunction "136_136") (pintype "passive"))
      (node (ref "J20") (pin "141") (pinfunction "141_141") (pintype "passive"))
      (node (ref "J20") (pin "142") (pinfunction "142_142") (pintype "passive"))
      (node (ref "J20") (pin "147") (pinfunction "147_147") (pintype "passive"))
      (node (ref "J20") (pin "148") (pinfunction "148_148") (pintype "passive"))
      (node (ref "J20") (pin "153") (pinfunction "153_153") (pintype "passive"))
      (node (ref "J20") (pin "154") (pinfunction "154_154") (pintype "passive"))
      (node (ref "J20") (pin "159") (pinfunction "159_159") (pintype "passive"))
      (node (ref "J20") (pin "160") (pinfunction "160_160") (pintype "passive"))
      (node (ref "J20") (pin "163") (pinfunction "163_163") (pintype "passive"))
      (node (ref "R234") (pin "1") (pinfunction "1_1") (pintype "passive"))
    )
    (net (code "155") (name "unconnected-(J20-Pad87)") (class "Default")
      (node (ref "J20") (pin "87") (pinfunction "87_87") (pintype "passive"))
    )
    (net (code "156") (name "unconnected-(J20-Pad88)") (class "Default")
      (node (ref "J20") (pin "88") (pinfunction "88_88") (pintype "passive"))
    )
    (net (code "157") (name "unconnected-(J20-Pad91)") (class "Default")
      (node (ref "J20") (pin "91") (pinfunction "91_91") (pintype "passive"))
    )
    (net (code "158") (name "unconnected-(J20-Pad92)") (class "Default")
      (node (ref "J20") (pin "92") (pinfunction "92_92") (pintype "passive"))
    )
    (net (code "159") (name "unconnected-(J20-Pad95)") (class "Default")
      (node (ref "J20") (pin "95") (pinfunction "95_95") (pintype "passive"))
    )
    (net (code "160") (name "unconnected-(J20-Pad96)") (class "Default")
      (node (ref "J20") (pin "96") (pinfunction "96_96") (pintype "passive"))
    )
    (net (code "161") (name "unconnected-(J20-Pad97)") (class "Default")
      (node (ref "J20") (pin "97") (pinfunction "97_97") (pintype "passive"))
    )
    (net (code "162") (name "unconnected-(J20-Pad100)") (class "Default")
      (node (ref "J20") (pin "100") (pinfunction "100_100") (pintype "passive"))
    )
    (net (code "163") (name "unconnected-(J20-Pad101)") (class "Default")
      (node (ref "J20") (pin "101") (pinfunction "101_101") (pintype "passive"))
    )
    (net (code "164") (name "unconnected-(J20-Pad104)") (class "Default")
      (node (ref "J20") (pin "104") (pinfunction "104_104") (pintype "passive"))
    )
    (net (code "165") (name "unconnected-(J20-Pad105)") (class "Default")
      (node (ref "J20") (pin "105") (pinfunction "105_105") (pintype "passive"))
    )
    (net (code "166") (name "unconnected-(J20-Pad110)") (class "Default")
      (node (ref "J20") (pin "110") (pinfunction "110_110") (pintype "passive"))
    )
    (net (code "167") (name "unconnected-(J20-Pad134)") (class "Default")
      (node (ref "J20") (pin "134") (pinfunction "134_134") (pintype "passive"))
    )
    (net (code "168") (name "unconnected-(J20-Pad157)") (class "Default")
      (node (ref "J20") (pin "157") (pinfunction "157_157") (pintype "passive"))
    )
    (net (code "169") (name "unconnected-(J20-Pad161)") (class "Default")
      (node (ref "J20") (pin "161") (pinfunction "161_161") (pintype "passive"))
    )
    (net (code "170") (name "unconnected-(J20-Pad162)") (class "Default")
      (node (ref "J20") (pin "162") (pinfunction "162_162") (pintype "passive"))
    )
    (net (code "171") (name "unconnected-(J20-Pad165)") (class "Default")
      (node (ref "J20") (pin "165") (pinfunction "165_165") (pintype "passive"))
    )
  )
)
